# A_R_A_2_0.net
KiCad netlist of a schematic drawn in EasyEDA Pro
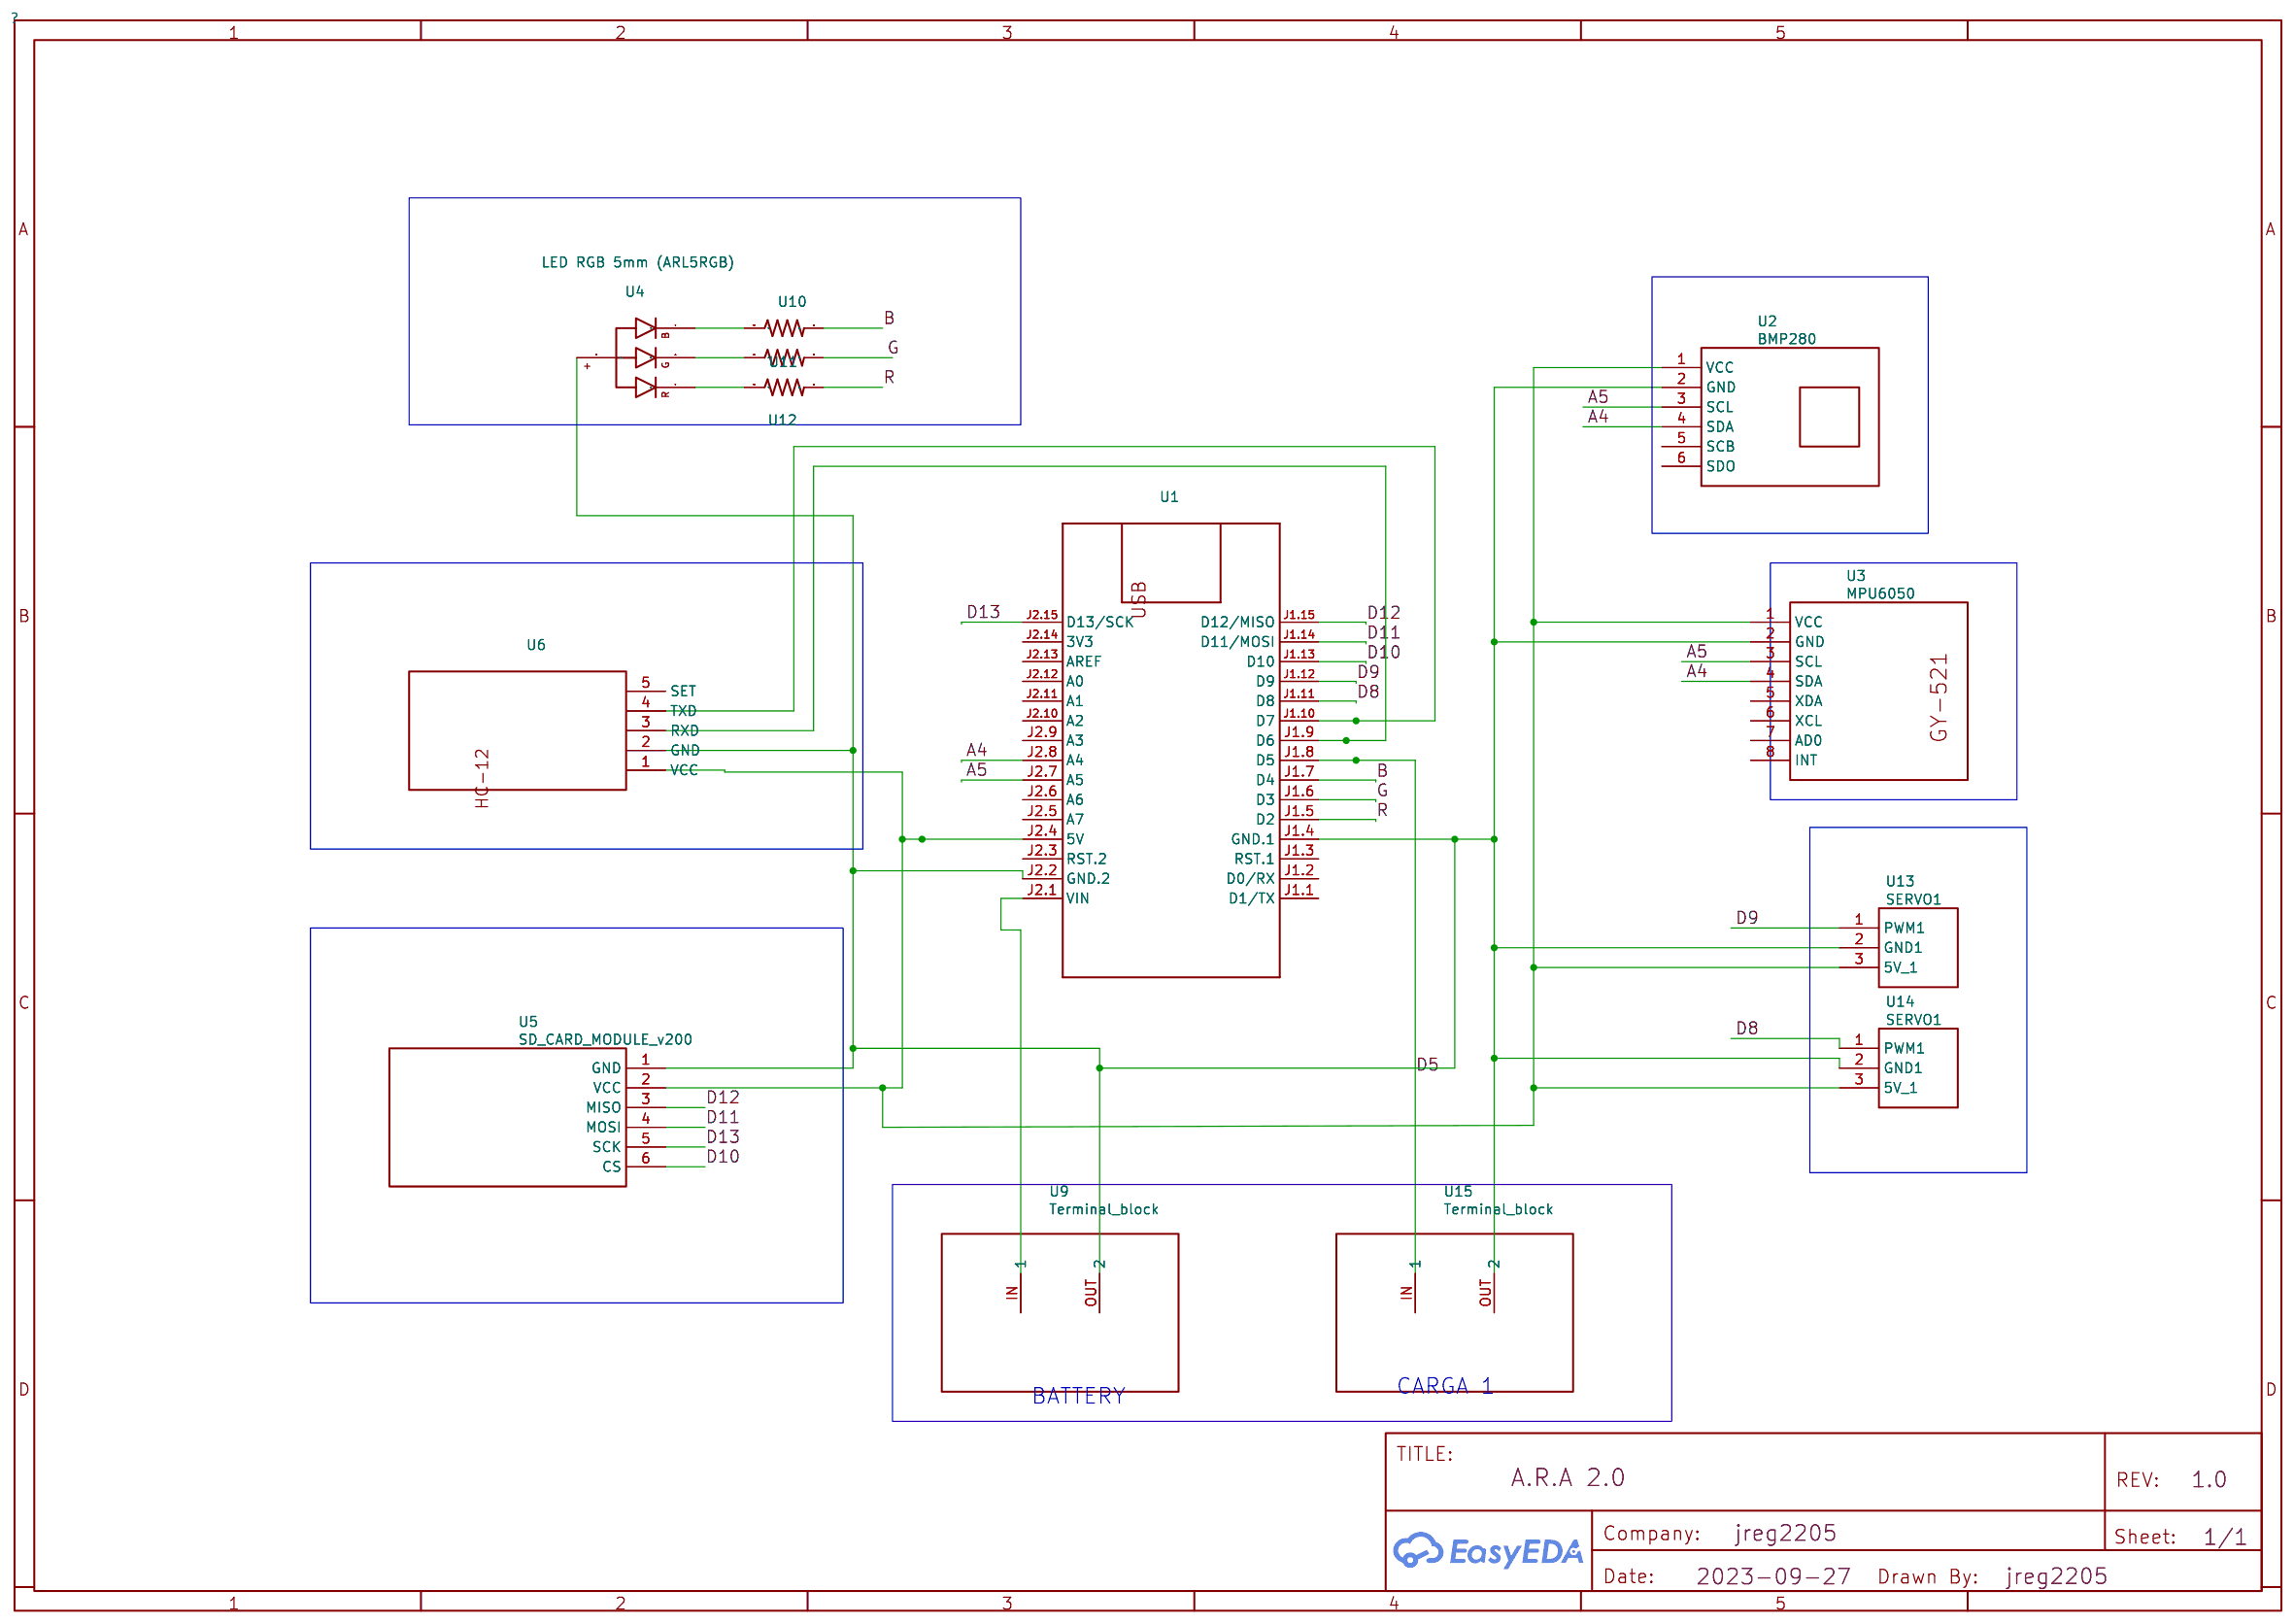
[diagram p0: schematic sheet]

(export (version "E")
  (design (tool "Eeschema 10.0.6"))
  (components
    (comp (ref "U1")
      (value "NO")
      (footprint "easyedapro:ARDUINO-NANO-3.0")
      (fields (field (name "Contributor") "santiagoM"))
      (libsource (lib "") (part "NO_2"))
    )
    (comp (ref "U2")
      (value "BMP280")
      (footprint "easyedapro:BMP280")
      (fields (field (name "Contributor") "modlfo"))
      (libsource (lib "easyedapro") (part "BMP280"))
    )
    (comp (ref "U3")
      (value "MPU6050")
      (footprint "easyedapro:MPU6050")
      (fields (field (name "Contributor") "lizzie"))
      (libsource (lib "easyedapro") (part "MPU6050"))
    )
    (comp (ref "U4")
      (value "LED RGB 5mm (ARL5RGB)")
      (footprint "easyedapro:LED RGB 5MM (ARL5RGB)")
      (fields (field (name "Contributor") "victornp22"))
      (libsource (lib "easyedapro") (part "LED RGB 5mm (ARL5RGB)"))
    )
    (comp (ref "U5")
      (value "SD_CARD_MODULE_v200")
      (footprint "easyedapro:SD_CARD_V20")
      (fields (field (name "Contributor") "jreg2205"))
      (libsource (lib "easyedapro") (part "SD_CARD_MODULE_v200"))
    )
    (comp (ref "U6")
      (value "NO")
      (footprint "easyedapro:HC-12 V2.0")
      (fields (field (name "Contributor") "jreg2205"))
      (libsource (lib "") (part "NO_1"))
    )
    (comp (ref "U9")
      (value "Terminal_block")
      (footprint "easyedapro:TERMINAL_BLOCK")
      (fields (field (name "Contributor") "jreg2205"))
      (libsource (lib "easyedapro") (part "Terminal_block"))
    )
    (comp (ref "U10")
      (value "NO")
      (footprint "easyedapro:AXIAL-0.3")
      (fields (field (name "Contributor") "jreg2205"))
      (libsource (lib "easyedapro") (part "NO"))
    )
    (comp (ref "U11")
      (value "NO")
      (footprint "easyedapro:AXIAL-0.3")
      (fields (field (name "Contributor") "jreg2205"))
      (libsource (lib "easyedapro") (part "NO"))
    )
    (comp (ref "U12")
      (value "NO")
      (footprint "easyedapro:AXIAL-0.3")
      (fields (field (name "Contributor") "jreg2205"))
      (libsource (lib "easyedapro") (part "NO"))
    )
    (comp (ref "U13")
      (value "SERVO1")
      (footprint "easyedapro:SERVO1")
      (fields (field (name "Contributor") "김동건"))
      (libsource (lib "easyedapro") (part "SERVO1"))
    )
    (comp (ref "U14")
      (value "SERVO1")
      (footprint "easyedapro:SERVO1")
      (fields (field (name "Contributor") "김동건"))
      (libsource (lib "easyedapro") (part "SERVO1"))
    )
    (comp (ref "U15")
      (value "Terminal_block")
      (footprint "easyedapro:TERMINAL_BLOCK")
      (fields (field (name "Contributor") "jreg2205"))
      (libsource (lib "easyedapro") (part "Terminal_block"))
    )
  )
  (nets
    (net (code "1") (name "/A4") (class "Default")
      (node (ref "U1") (pin "J2.8") (pinfunction "A4_J2.8") (pintype "bidirectional"))
      (node (ref "U2") (pin "4") (pinfunction "SDA_4") (pintype "unspecified"))
      (node (ref "U3") (pin "4") (pinfunction "SDA_4") (pintype "unspecified"))
    )
    (net (code "2") (name "/A5") (class "Default")
      (node (ref "U1") (pin "J2.7") (pinfunction "A5_J2.7") (pintype "bidirectional"))
      (node (ref "U2") (pin "3") (pinfunction "SCL_3") (pintype "unspecified"))
      (node (ref "U3") (pin "3") (pinfunction "SCL_3") (pintype "unspecified"))
    )
    (net (code "3") (name "/B") (class "Default")
      (node (ref "U1") (pin "J1.7") (pinfunction "D4_J1.7") (pintype "bidirectional"))
      (node (ref "U10") (pin "P$2") (pinfunction "2_P$2") (pintype "bidirectional"))
    )
    (net (code "4") (name "/D5") (class "Default")
      (node (ref "U1") (pin "J1.8") (pinfunction "D5_J1.8") (pintype "bidirectional"))
      (node (ref "U15") (pin "IN") (pinfunction "1_IN") (pintype "unspecified"))
    )
    (net (code "5") (name "/D8") (class "Default")
      (node (ref "U1") (pin "J1.11") (pinfunction "D8_J1.11") (pintype "bidirectional"))
      (node (ref "U14") (pin "1") (pinfunction "PWM1_1") (pintype "unspecified"))
    )
    (net (code "6") (name "/D9") (class "Default")
      (node (ref "U1") (pin "J1.12") (pinfunction "D9_J1.12") (pintype "bidirectional"))
      (node (ref "U13") (pin "1") (pinfunction "PWM1_1") (pintype "unspecified"))
    )
    (net (code "7") (name "/D10") (class "Default")
      (node (ref "U1") (pin "J1.13") (pinfunction "D10_J1.13") (pintype "bidirectional"))
      (node (ref "U5") (pin "6") (pinfunction "CS_6") (pintype "unspecified"))
    )
    (net (code "8") (name "/D11") (class "Default")
      (node (ref "U1") (pin "J1.14") (pinfunction "D11/MOSI_J1.14") (pintype "bidirectional"))
      (node (ref "U5") (pin "4") (pinfunction "MOSI_4") (pintype "unspecified"))
    )
    (net (code "9") (name "/D12") (class "Default")
      (node (ref "U1") (pin "J1.15") (pinfunction "D12/MISO_J1.15") (pintype "bidirectional"))
      (node (ref "U5") (pin "3") (pinfunction "MISO_3") (pintype "unspecified"))
    )
    (net (code "10") (name "/D13") (class "Default")
      (node (ref "U1") (pin "J2.15") (pinfunction "D13/SCK_J2.15") (pintype "bidirectional"))
      (node (ref "U5") (pin "5") (pinfunction "SCK_5") (pintype "unspecified"))
    )
    (net (code "11") (name "/G") (class "Default")
      (node (ref "U1") (pin "J1.6") (pinfunction "D3_J1.6") (pintype "bidirectional"))
      (node (ref "U11") (pin "P$2") (pinfunction "2_P$2") (pintype "bidirectional"))
    )
    (net (code "12") (name "/R") (class "Default")
      (node (ref "U1") (pin "J1.5") (pinfunction "D2_J1.5") (pintype "bidirectional"))
      (node (ref "U12") (pin "P$2") (pinfunction "2_P$2") (pintype "bidirectional"))
    )
    (net (code "13") (name "Net-(U1-5V)") (class "Default")
      (node (ref "U1") (pin "J2.4") (pinfunction "5V_J2.4") (pintype "bidirectional"))
      (node (ref "U13") (pin "3") (pinfunction "5V_1_3") (pintype "unspecified"))
      (node (ref "U14") (pin "3") (pinfunction "5V_1_3") (pintype "unspecified"))
      (node (ref "U2") (pin "1") (pinfunction "VCC_1") (pintype "unspecified"))
      (node (ref "U3") (pin "1") (pinfunction "VCC_1") (pintype "unspecified"))
      (node (ref "U5") (pin "2") (pinfunction "VCC_2") (pintype "unspecified"))
      (node (ref "U6") (pin "1") (pinfunction "VCC_1") (pintype "unspecified"))
    )
    (net (code "14") (name "Net-(U1-D6)") (class "Default")
      (node (ref "U1") (pin "J1.9") (pinfunction "D6_J1.9") (pintype "bidirectional"))
      (node (ref "U6") (pin "3") (pinfunction "RXD_3") (pintype "unspecified"))
    )
    (net (code "15") (name "Net-(U1-D7)") (class "Default")
      (node (ref "U1") (pin "J1.10") (pinfunction "D7_J1.10") (pintype "bidirectional"))
      (node (ref "U6") (pin "4") (pinfunction "TXD_4") (pintype "unspecified"))
    )
    (net (code "16") (name "Net-(U1-GND.1)") (class "Default")
      (node (ref "U1") (pin "J1.4") (pinfunction "GND.1_J1.4") (pintype "bidirectional"))
      (node (ref "U1") (pin "J2.2") (pinfunction "GND.2_J2.2") (pintype "bidirectional"))
      (node (ref "U13") (pin "2") (pinfunction "GND1_2") (pintype "unspecified"))
      (node (ref "U14") (pin "2") (pinfunction "GND1_2") (pintype "unspecified"))
      (node (ref "U15") (pin "OUT") (pinfunction "2_OUT") (pintype "unspecified"))
      (node (ref "U2") (pin "2") (pinfunction "GND_2") (pintype "unspecified"))
      (node (ref "U3") (pin "2") (pinfunction "GND_2") (pintype "unspecified"))
      (node (ref "U4") (pin "2") (pinfunction "2_2") (pintype "unspecified"))
      (node (ref "U5") (pin "1") (pinfunction "GND_1") (pintype "unspecified"))
      (node (ref "U6") (pin "2") (pinfunction "GND_2") (pintype "unspecified"))
      (node (ref "U9") (pin "OUT") (pinfunction "2_OUT") (pintype "unspecified"))
    )
    (net (code "17") (name "Net-(U1-VIN)") (class "Default")
      (node (ref "U1") (pin "J2.1") (pinfunction "VIN_J2.1") (pintype "bidirectional"))
      (node (ref "U9") (pin "IN") (pinfunction "1_IN") (pintype "unspecified"))
    )
    (net (code "18") (name "Net-(U10-1)") (class "Default")
      (node (ref "U10") (pin "P$1") (pinfunction "1_P$1") (pintype "bidirectional"))
      (node (ref "U4") (pin "4") (pinfunction "4_4") (pintype "unspecified"))
    )
    (net (code "19") (name "Net-(U11-1)") (class "Default")
      (node (ref "U11") (pin "P$1") (pinfunction "1_P$1") (pintype "bidirectional"))
      (node (ref "U4") (pin "3") (pinfunction "3_3") (pintype "unspecified"))
    )
    (net (code "20") (name "Net-(U12-1)") (class "Default")
      (node (ref "U12") (pin "P$1") (pinfunction "1_P$1") (pintype "bidirectional"))
      (node (ref "U4") (pin "1") (pinfunction "1_1") (pintype "unspecified"))
    )
    (net (code "21") (name "unconnected-(U1-3V3-PadJ2.14)") (class "Default")
      (node (ref "U1") (pin "J2.14") (pinfunction "3V3_J2.14") (pintype "bidirectional"))
    )
    (net (code "22") (name "unconnected-(U1-A0-PadJ2.12)") (class "Default")
      (node (ref "U1") (pin "J2.12") (pinfunction "A0_J2.12") (pintype "bidirectional"))
    )
    (net (code "23") (name "unconnected-(U1-A1-PadJ2.11)") (class "Default")
      (node (ref "U1") (pin "J2.11") (pinfunction "A1_J2.11") (pintype "bidirectional"))
    )
    (net (code "24") (name "unconnected-(U1-A2-PadJ2.10)") (class "Default")
      (node (ref "U1") (pin "J2.10") (pinfunction "A2_J2.10") (pintype "bidirectional"))
    )
    (net (code "25") (name "unconnected-(U1-A3-PadJ2.9)") (class "Default")
      (node (ref "U1") (pin "J2.9") (pinfunction "A3_J2.9") (pintype "bidirectional"))
    )
    (net (code "26") (name "unconnected-(U1-A6-PadJ2.6)") (class "Default")
      (node (ref "U1") (pin "J2.6") (pinfunction "A6_J2.6") (pintype "bidirectional"))
    )
    (net (code "27") (name "unconnected-(U1-A7-PadJ2.5)") (class "Default")
      (node (ref "U1") (pin "J2.5") (pinfunction "A7_J2.5") (pintype "bidirectional"))
    )
    (net (code "28") (name "unconnected-(U1-AREF-PadJ2.13)") (class "Default")
      (node (ref "U1") (pin "J2.13") (pinfunction "AREF_J2.13") (pintype "bidirectional"))
    )
    (net (code "29") (name "unconnected-(U1-D0{slash}RX-PadJ1.2)") (class "Default")
      (node (ref "U1") (pin "J1.2") (pinfunction "D0/RX_J1.2") (pintype "bidirectional"))
    )
    (net (code "30") (name "unconnected-(U1-D1{slash}TX-PadJ1.1)") (class "Default")
      (node (ref "U1") (pin "J1.1") (pinfunction "D1/TX_J1.1") (pintype "bidirectional"))
    )
    (net (code "31") (name "unconnected-(U1-RST.1-PadJ1.3)") (class "Default")
      (node (ref "U1") (pin "J1.3") (pinfunction "RST.1_J1.3") (pintype "bidirectional"))
    )
    (net (code "32") (name "unconnected-(U1-RST.2-PadJ2.3)") (class "Default")
      (node (ref "U1") (pin "J2.3") (pinfunction "RST.2_J2.3") (pintype "bidirectional"))
    )
    (net (code "33") (name "unconnected-(U2-SCB-Pad5)") (class "Default")
      (node (ref "U2") (pin "5") (pinfunction "SCB_5") (pintype "unspecified"))
    )
    (net (code "34") (name "unconnected-(U2-SDO-Pad6)") (class "Default")
      (node (ref "U2") (pin "6") (pinfunction "SDO_6") (pintype "unspecified"))
    )
    (net (code "35") (name "unconnected-(U3-AD0-Pad7)") (class "Default")
      (node (ref "U3") (pin "7") (pinfunction "AD0_7") (pintype "unspecified"))
    )
    (net (code "36") (name "unconnected-(U3-INT-Pad8)") (class "Default")
      (node (ref "U3") (pin "8") (pinfunction "INT_8") (pintype "unspecified"))
    )
    (net (code "37") (name "unconnected-(U3-XCL-Pad6)") (class "Default")
      (node (ref "U3") (pin "6") (pinfunction "XCL_6") (pintype "unspecified"))
    )
    (net (code "38") (name "unconnected-(U3-XDA-Pad5)") (class "Default")
      (node (ref "U3") (pin "5") (pinfunction "XDA_5") (pintype "unspecified"))
    )
    (net (code "39") (name "unconnected-(U6-SET-Pad5)") (class "Default")
      (node (ref "U6") (pin "5") (pinfunction "SET_5") (pintype "unspecified"))
    )
  )
)
